# stm32_2.net
KiCad netlist of a schematic drawn in EasyEDA
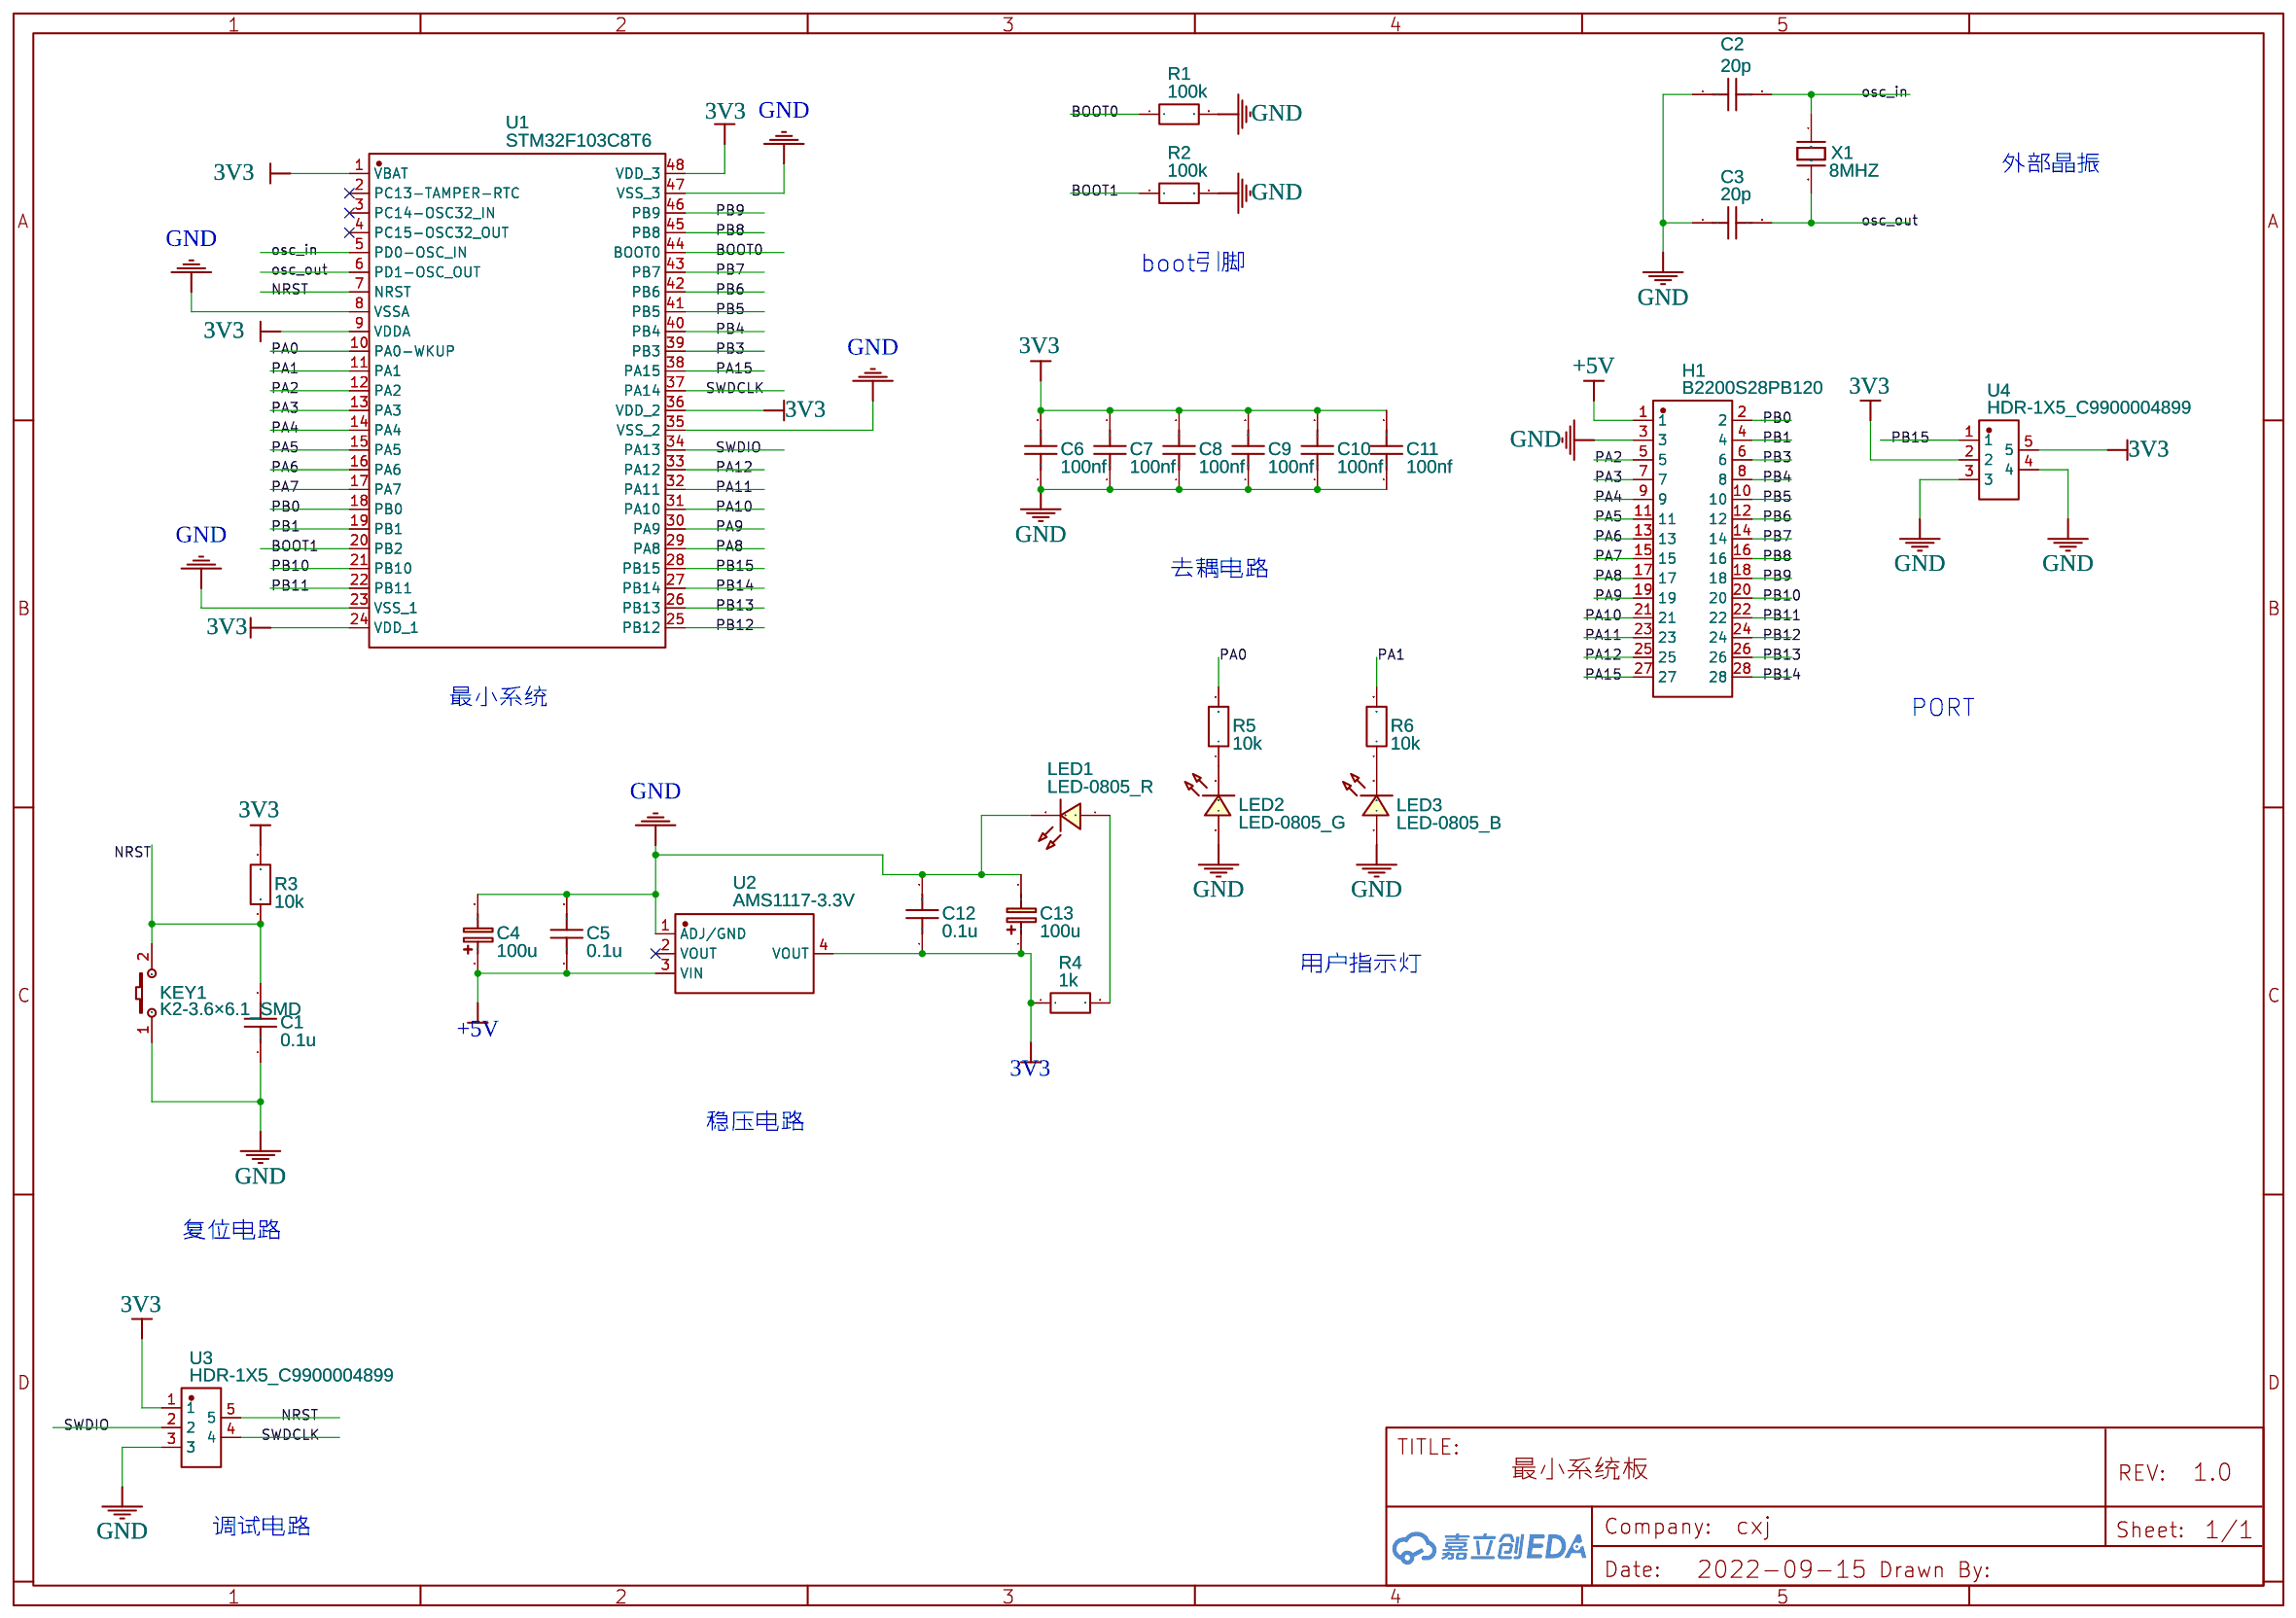
[diagram p0: schematic sheet]

(export (version "E")
  (design (tool "Eeschema 10.0.6"))
  (components
    (comp (ref "C1") (value "0.1u") (libsource (lib "") (part "C_0603_US")))
    (comp (ref "C2") (value "20p") (libsource (lib "") (part "C_0603_US_1")))
    (comp (ref "C3") (value "20p") (libsource (lib "") (part "C_0603_US_1")))
    (comp (ref "C4") (value "100u") (libsource (lib "") (part "C_Tan_SMD_A_EU")))
    (comp (ref "C5") (value "0.1u") (libsource (lib "") (part "C_0805_US")))
    (comp (ref "C6") (value "100nf") (libsource (lib "") (part "C_0603_US")))
    (comp (ref "C7") (value "100nf") (libsource (lib "") (part "C_0603_US")))
    (comp (ref "C8") (value "100nf") (libsource (lib "") (part "C_0603_US")))
    (comp (ref "C9") (value "100nf") (libsource (lib "") (part "C_0603_US")))
    (comp (ref "C10") (value "100nf") (libsource (lib "") (part "C_0603_US")))
    (comp (ref "C11") (value "100nf") (libsource (lib "") (part "C_0603_US")))
    (comp (ref "C12") (value "0.1u") (libsource (lib "") (part "C_0805_US")))
    (comp (ref "C13") (value "100u") (libsource (lib "") (part "C_Tan_SMD_A_EU_1")))
    (comp (ref "H1")
      (value "B2200S28PB120")
      (fields (field (name "BOM_Supplier Part") "C379815"))
      (libsource (lib "") (part "B2200S28PB120"))
    )
    (comp (ref "KEY1")
      (value "K2-3.6×6.1_SMD")
      (fields
        (field (name "BOM_Manufacturer Part") "K2-1107ST-A4SW-06")
        (field (name "BOM_Supplier Part") "C118141")
      )
      (libsource (lib "") (part "K2-3.6×6.1_SMD"))
    )
    (comp (ref "LED1")
      (value "LED-0805_R")
      (fields
        (field (name "BOM_Manufacturer Part") "19-217/R6C-AL1M2VY/3T")
        (field (name "BOM_Supplier Part") "C72044")
      )
      (libsource (lib "") (part "LED-0603_R"))
    )
    (comp (ref "LED2")
      (value "LED-0805_G")
      (fields (field (name "BOM_Manufacturer Part") "NCD0805G1") (field (name "BOM_Supplier Part") "C84260"))
      (libsource (lib "") (part "LED-0805_G"))
    )
    (comp (ref "LED3")
      (value "LED-0805_B")
      (fields
        (field (name "BOM_Manufacturer Part") "D-B080508B1-KS2")
        (field (name "BOM_Supplier Part") "C108412")
      )
      (libsource (lib "") (part "LED-0805_B"))
    )
    (comp (ref "R1") (value "100k") (libsource (lib "") (part "R_0603_EU")))
    (comp (ref "R2") (value "100k") (libsource (lib "") (part "R_0603_EU")))
    (comp (ref "R3") (value "10k") (libsource (lib "") (part "R_0603_EU_1")))
    (comp (ref "R4") (value "1k") (libsource (lib "") (part "R_0805_EU_1")))
    (comp (ref "R5") (value "10k") (libsource (lib "") (part "R_0805_EU")))
    (comp (ref "R6") (value "10k") (libsource (lib "") (part "R_0805_EU")))
    (comp (ref "U1")
      (value "STM32F103C8T6")
      (fields (field (name "BOM_Supplier Part") "C8734"))
      (libsource (lib "") (part "STM32F103C8T6"))
    )
    (comp (ref "U2")
      (value "AMS1117-3.3V")
      (fields (field (name "BOM_Supplier Part") "C2688239"))
      (libsource (lib "") (part "AMS1117-3.3V"))
    )
    (comp (ref "U3")
      (value "HDR-1X5_C9900004899")
      (fields
        (field (name "BOM_Manufacturer Part") "HDR-1X5")
        (field (name "BOM_Supplier Part") "C9900004899")
      )
      (libsource (lib "") (part "HDR-1X5_C9900004899"))
    )
    (comp (ref "U4")
      (value "HDR-1X5_C9900004899")
      (fields
        (field (name "BOM_Manufacturer Part") "HDR-1X5")
        (field (name "BOM_Supplier Part") "C9900004899")
      )
      (libsource (lib "") (part "HDR-1X5_C9900004899"))
    )
    (comp (ref "X1")
      (value "8MHZ")
      (fields
        (field (name "BOM_Manufacturer Part") "X49SM12MSD2SC")
        (field (name "BOM_Supplier Part") "undefined")
      )
      (libsource (lib "") (part "12MHZ"))
    )
  )
  (nets
    (net (code "1") (name "+5V") (class "Default")
      (node (ref "C4") (pin "1") (pinfunction "1_1") (pintype "unspecified"))
      (node (ref "C5") (pin "1") (pinfunction "1_1") (pintype "unspecified"))
      (node (ref "H1") (pin "1") (pinfunction "1_1") (pintype "unspecified"))
      (node (ref "U2") (pin "3") (pinfunction "VIN_3") (pintype "unspecified"))
    )
    (net (code "2") (name "/BOOT0") (class "Default")
      (node (ref "R1") (pin "1") (pinfunction "1_1") (pintype "unspecified"))
      (node (ref "U1") (pin "44") (pinfunction "BOOT0_44") (pintype "unspecified"))
    )
    (net (code "3") (name "/BOOT1") (class "Default")
      (node (ref "R2") (pin "1") (pinfunction "1_1") (pintype "unspecified"))
      (node (ref "U1") (pin "20") (pinfunction "PB2_20") (pintype "unspecified"))
    )
    (net (code "4") (name "/NRST") (class "Default")
      (node (ref "C1") (pin "2") (pinfunction "2_2") (pintype "unspecified"))
      (node (ref "KEY1") (pin "2") (pinfunction "2_2") (pintype "unspecified"))
      (node (ref "R3") (pin "1") (pinfunction "1_1") (pintype "unspecified"))
      (node (ref "U1") (pin "7") (pinfunction "NRST_7") (pintype "unspecified"))
      (node (ref "U3") (pin "5") (pinfunction "5_5") (pintype "unspecified"))
    )
    (net (code "5") (name "/PA0") (class "Default")
      (node (ref "R5") (pin "2") (pinfunction "2_2") (pintype "unspecified"))
      (node (ref "U1") (pin "10") (pinfunction "PA0-WKUP_10") (pintype "unspecified"))
    )
    (net (code "6") (name "/PA1") (class "Default")
      (node (ref "R6") (pin "2") (pinfunction "2_2") (pintype "unspecified"))
      (node (ref "U1") (pin "11") (pinfunction "PA1_11") (pintype "unspecified"))
    )
    (net (code "7") (name "/PA2") (class "Default")
      (node (ref "H1") (pin "5") (pinfunction "5_5") (pintype "unspecified"))
      (node (ref "U1") (pin "12") (pinfunction "PA2_12") (pintype "unspecified"))
    )
    (net (code "8") (name "/PA3") (class "Default")
      (node (ref "H1") (pin "7") (pinfunction "7_7") (pintype "unspecified"))
      (node (ref "U1") (pin "13") (pinfunction "PA3_13") (pintype "unspecified"))
    )
    (net (code "9") (name "/PA4") (class "Default")
      (node (ref "H1") (pin "9") (pinfunction "9_9") (pintype "unspecified"))
      (node (ref "U1") (pin "14") (pinfunction "PA4_14") (pintype "unspecified"))
    )
    (net (code "10") (name "/PA5") (class "Default")
      (node (ref "H1") (pin "11") (pinfunction "11_11") (pintype "unspecified"))
      (node (ref "U1") (pin "15") (pinfunction "PA5_15") (pintype "unspecified"))
    )
    (net (code "11") (name "/PA6") (class "Default")
      (node (ref "H1") (pin "13") (pinfunction "13_13") (pintype "unspecified"))
      (node (ref "U1") (pin "16") (pinfunction "PA6_16") (pintype "unspecified"))
    )
    (net (code "12") (name "/PA7") (class "Default")
      (node (ref "H1") (pin "15") (pinfunction "15_15") (pintype "unspecified"))
      (node (ref "U1") (pin "17") (pinfunction "PA7_17") (pintype "unspecified"))
    )
    (net (code "13") (name "/PA8") (class "Default")
      (node (ref "H1") (pin "17") (pinfunction "17_17") (pintype "unspecified"))
      (node (ref "U1") (pin "29") (pinfunction "PA8_29") (pintype "unspecified"))
    )
    (net (code "14") (name "/PA9") (class "Default")
      (node (ref "H1") (pin "19") (pinfunction "19_19") (pintype "unspecified"))
      (node (ref "U1") (pin "30") (pinfunction "PA9_30") (pintype "unspecified"))
    )
    (net (code "15") (name "/PA10") (class "Default")
      (node (ref "H1") (pin "21") (pinfunction "21_21") (pintype "unspecified"))
      (node (ref "U1") (pin "31") (pinfunction "PA10_31") (pintype "unspecified"))
    )
    (net (code "16") (name "/PA11") (class "Default")
      (node (ref "H1") (pin "23") (pinfunction "23_23") (pintype "unspecified"))
      (node (ref "U1") (pin "32") (pinfunction "PA11_32") (pintype "unspecified"))
    )
    (net (code "17") (name "/PA12") (class "Default")
      (node (ref "H1") (pin "25") (pinfunction "25_25") (pintype "unspecified"))
      (node (ref "U1") (pin "33") (pinfunction "PA12_33") (pintype "unspecified"))
    )
    (net (code "18") (name "/PA15") (class "Default")
      (node (ref "H1") (pin "27") (pinfunction "27_27") (pintype "unspecified"))
      (node (ref "U1") (pin "38") (pinfunction "PA15_38") (pintype "unspecified"))
    )
    (net (code "19") (name "/PB0") (class "Default")
      (node (ref "H1") (pin "2") (pinfunction "2_2") (pintype "unspecified"))
      (node (ref "U1") (pin "18") (pinfunction "PB0_18") (pintype "unspecified"))
    )
    (net (code "20") (name "/PB1") (class "Default")
      (node (ref "H1") (pin "4") (pinfunction "4_4") (pintype "unspecified"))
      (node (ref "U1") (pin "19") (pinfunction "PB1_19") (pintype "unspecified"))
    )
    (net (code "21") (name "/PB3") (class "Default")
      (node (ref "H1") (pin "6") (pinfunction "6_6") (pintype "unspecified"))
      (node (ref "U1") (pin "39") (pinfunction "PB3_39") (pintype "unspecified"))
    )
    (net (code "22") (name "/PB4") (class "Default")
      (node (ref "H1") (pin "8") (pinfunction "8_8") (pintype "unspecified"))
      (node (ref "U1") (pin "40") (pinfunction "PB4_40") (pintype "unspecified"))
    )
    (net (code "23") (name "/PB5") (class "Default")
      (node (ref "H1") (pin "10") (pinfunction "10_10") (pintype "unspecified"))
      (node (ref "U1") (pin "41") (pinfunction "PB5_41") (pintype "unspecified"))
    )
    (net (code "24") (name "/PB6") (class "Default")
      (node (ref "H1") (pin "12") (pinfunction "12_12") (pintype "unspecified"))
      (node (ref "U1") (pin "42") (pinfunction "PB6_42") (pintype "unspecified"))
    )
    (net (code "25") (name "/PB7") (class "Default")
      (node (ref "H1") (pin "14") (pinfunction "14_14") (pintype "unspecified"))
      (node (ref "U1") (pin "43") (pinfunction "PB7_43") (pintype "unspecified"))
    )
    (net (code "26") (name "/PB8") (class "Default")
      (node (ref "H1") (pin "16") (pinfunction "16_16") (pintype "unspecified"))
      (node (ref "U1") (pin "45") (pinfunction "PB8_45") (pintype "unspecified"))
    )
    (net (code "27") (name "/PB9") (class "Default")
      (node (ref "H1") (pin "18") (pinfunction "18_18") (pintype "unspecified"))
      (node (ref "U1") (pin "46") (pinfunction "PB9_46") (pintype "unspecified"))
    )
    (net (code "28") (name "/PB10") (class "Default")
      (node (ref "H1") (pin "20") (pinfunction "20_20") (pintype "unspecified"))
      (node (ref "U1") (pin "21") (pinfunction "PB10_21") (pintype "unspecified"))
    )
    (net (code "29") (name "/PB11") (class "Default")
      (node (ref "H1") (pin "22") (pinfunction "22_22") (pintype "unspecified"))
      (node (ref "U1") (pin "22") (pinfunction "PB11_22") (pintype "unspecified"))
    )
    (net (code "30") (name "/PB12") (class "Default")
      (node (ref "H1") (pin "24") (pinfunction "24_24") (pintype "unspecified"))
      (node (ref "U1") (pin "25") (pinfunction "PB12_25") (pintype "unspecified"))
    )
    (net (code "31") (name "/PB13") (class "Default")
      (node (ref "H1") (pin "26") (pinfunction "26_26") (pintype "unspecified"))
      (node (ref "U1") (pin "26") (pinfunction "PB13_26") (pintype "unspecified"))
    )
    (net (code "32") (name "/PB14") (class "Default")
      (node (ref "H1") (pin "28") (pinfunction "28_28") (pintype "unspecified"))
      (node (ref "U1") (pin "27") (pinfunction "PB14_27") (pintype "unspecified"))
    )
    (net (code "33") (name "/PB15") (class "Default")
      (node (ref "U1") (pin "28") (pinfunction "PB15_28") (pintype "unspecified"))
      (node (ref "U4") (pin "1") (pinfunction "1_1") (pintype "unspecified"))
    )
    (net (code "34") (name "/SWDCLK") (class "Default")
      (node (ref "U1") (pin "37") (pinfunction "PA14_37") (pintype "unspecified"))
      (node (ref "U3") (pin "4") (pinfunction "4_4") (pintype "unspecified"))
    )
    (net (code "35") (name "/SWDIO") (class "Default")
      (node (ref "U1") (pin "34") (pinfunction "PA13_34") (pintype "unspecified"))
      (node (ref "U3") (pin "2") (pinfunction "2_2") (pintype "unspecified"))
    )
    (net (code "36") (name "/osc_in") (class "Default")
      (node (ref "C2") (pin "2") (pinfunction "2_2") (pintype "unspecified"))
      (node (ref "U1") (pin "5") (pinfunction "PD0-OSC_IN_5") (pintype "unspecified"))
      (node (ref "X1") (pin "1") (pinfunction "OSC1_1") (pintype "input"))
    )
    (net (code "37") (name "/osc_out") (class "Default")
      (node (ref "C3") (pin "2") (pinfunction "2_2") (pintype "unspecified"))
      (node (ref "U1") (pin "6") (pinfunction "PD1-OSC_OUT_6") (pintype "unspecified"))
      (node (ref "X1") (pin "2") (pinfunction "OSC2_2") (pintype "input"))
    )
    (net (code "38") (name "3V3") (class "Default")
      (node (ref "C10") (pin "2") (pinfunction "2_2") (pintype "unspecified"))
      (node (ref "C11") (pin "2") (pinfunction "2_2") (pintype "unspecified"))
      (node (ref "C12") (pin "1") (pinfunction "1_1") (pintype "unspecified"))
      (node (ref "C13") (pin "1") (pinfunction "1_1") (pintype "unspecified"))
      (node (ref "C6") (pin "2") (pinfunction "2_2") (pintype "unspecified"))
      (node (ref "C7") (pin "2") (pinfunction "2_2") (pintype "unspecified"))
      (node (ref "C8") (pin "2") (pinfunction "2_2") (pintype "unspecified"))
      (node (ref "C9") (pin "2") (pinfunction "2_2") (pintype "unspecified"))
      (node (ref "R3") (pin "2") (pinfunction "2_2") (pintype "unspecified"))
      (node (ref "R4") (pin "1") (pinfunction "1_1") (pintype "unspecified"))
      (node (ref "U1") (pin "1") (pinfunction "VBAT_1") (pintype "unspecified"))
      (node (ref "U1") (pin "24") (pinfunction "VDD_1_24") (pintype "unspecified"))
      (node (ref "U1") (pin "36") (pinfunction "VDD_2_36") (pintype "unspecified"))
      (node (ref "U1") (pin "48") (pinfunction "VDD_3_48") (pintype "unspecified"))
      (node (ref "U1") (pin "9") (pinfunction "VDDA_9") (pintype "unspecified"))
      (node (ref "U2") (pin "4") (pinfunction "VOUT_4") (pintype "unspecified"))
      (node (ref "U3") (pin "1") (pinfunction "1_1") (pintype "unspecified"))
      (node (ref "U4") (pin "2") (pinfunction "2_2") (pintype "unspecified"))
      (node (ref "U4") (pin "5") (pinfunction "5_5") (pintype "unspecified"))
    )
    (net (code "39") (name "GND") (class "Default")
      (node (ref "C1") (pin "1") (pinfunction "1_1") (pintype "unspecified"))
      (node (ref "C10") (pin "1") (pinfunction "1_1") (pintype "unspecified"))
      (node (ref "C11") (pin "1") (pinfunction "1_1") (pintype "unspecified"))
      (node (ref "C12") (pin "2") (pinfunction "2_2") (pintype "unspecified"))
      (node (ref "C13") (pin "2") (pinfunction "2_2") (pintype "unspecified"))
      (node (ref "C2") (pin "1") (pinfunction "1_1") (pintype "unspecified"))
      (node (ref "C3") (pin "1") (pinfunction "1_1") (pintype "unspecified"))
      (node (ref "C4") (pin "2") (pinfunction "2_2") (pintype "unspecified"))
      (node (ref "C5") (pin "2") (pinfunction "2_2") (pintype "unspecified"))
      (node (ref "C6") (pin "1") (pinfunction "1_1") (pintype "unspecified"))
      (node (ref "C7") (pin "1") (pinfunction "1_1") (pintype "unspecified"))
      (node (ref "C8") (pin "1") (pinfunction "1_1") (pintype "unspecified"))
      (node (ref "C9") (pin "1") (pinfunction "1_1") (pintype "unspecified"))
      (node (ref "H1") (pin "3") (pinfunction "3_3") (pintype "unspecified"))
      (node (ref "KEY1") (pin "1") (pinfunction "1_1") (pintype "unspecified"))
      (node (ref "LED1") (pin "2") (pinfunction "2_2") (pintype "unspecified"))
      (node (ref "LED2") (pin "1") (pinfunction "1_1") (pintype "unspecified"))
      (node (ref "LED3") (pin "1") (pinfunction "1_1") (pintype "unspecified"))
      (node (ref "R1") (pin "2") (pinfunction "2_2") (pintype "unspecified"))
      (node (ref "R2") (pin "2") (pinfunction "2_2") (pintype "unspecified"))
      (node (ref "U1") (pin "23") (pinfunction "VSS_1_23") (pintype "unspecified"))
      (node (ref "U1") (pin "35") (pinfunction "VSS_2_35") (pintype "unspecified"))
      (node (ref "U1") (pin "47") (pinfunction "VSS_3_47") (pintype "unspecified"))
      (node (ref "U1") (pin "8") (pinfunction "VSSA_8") (pintype "unspecified"))
      (node (ref "U2") (pin "1") (pinfunction "ADJ/GND_1") (pintype "unspecified"))
      (node (ref "U3") (pin "3") (pinfunction "3_3") (pintype "unspecified"))
      (node (ref "U4") (pin "3") (pinfunction "3_3") (pintype "unspecified"))
      (node (ref "U4") (pin "4") (pinfunction "4_4") (pintype "unspecified"))
    )
    (net (code "40") (name "Net-(LED1-Pad1)") (class "Default")
      (node (ref "LED1") (pin "1") (pinfunction "1_1") (pintype "unspecified"))
      (node (ref "R4") (pin "2") (pinfunction "2_2") (pintype "unspecified"))
    )
    (net (code "41") (name "Net-(LED2-Pad2)") (class "Default")
      (node (ref "LED2") (pin "2") (pinfunction "2_2") (pintype "unspecified"))
      (node (ref "R5") (pin "1") (pinfunction "1_1") (pintype "unspecified"))
    )
    (net (code "42") (name "Net-(LED3-Pad2)") (class "Default")
      (node (ref "LED3") (pin "2") (pinfunction "2_2") (pintype "unspecified"))
      (node (ref "R6") (pin "1") (pinfunction "1_1") (pintype "unspecified"))
    )
    (net (code "43") (name "unconnected-(U1-PC13-TAMPER-RTC-Pad2)") (class "Default")
      (node (ref "U1") (pin "2") (pinfunction "PC13-TAMPER-RTC_2") (pintype "unspecified+no_connect"))
    )
    (net (code "44") (name "unconnected-(U1-PC14-OSC32_IN-Pad3)") (class "Default")
      (node (ref "U1") (pin "3") (pinfunction "PC14-OSC32_IN_3") (pintype "unspecified+no_connect"))
    )
    (net (code "45") (name "unconnected-(U1-PC15-OSC32_OUT-Pad4)") (class "Default")
      (node (ref "U1") (pin "4") (pinfunction "PC15-OSC32_OUT_4") (pintype "unspecified+no_connect"))
    )
    (net (code "46") (name "unconnected-(U2-VOUT-Pad2)") (class "Default")
      (node (ref "U2") (pin "2") (pinfunction "VOUT_2") (pintype "unspecified+no_connect"))
    )
  )
)
